# Power.net
KiCad netlist of a schematic drawn in Altium Designer
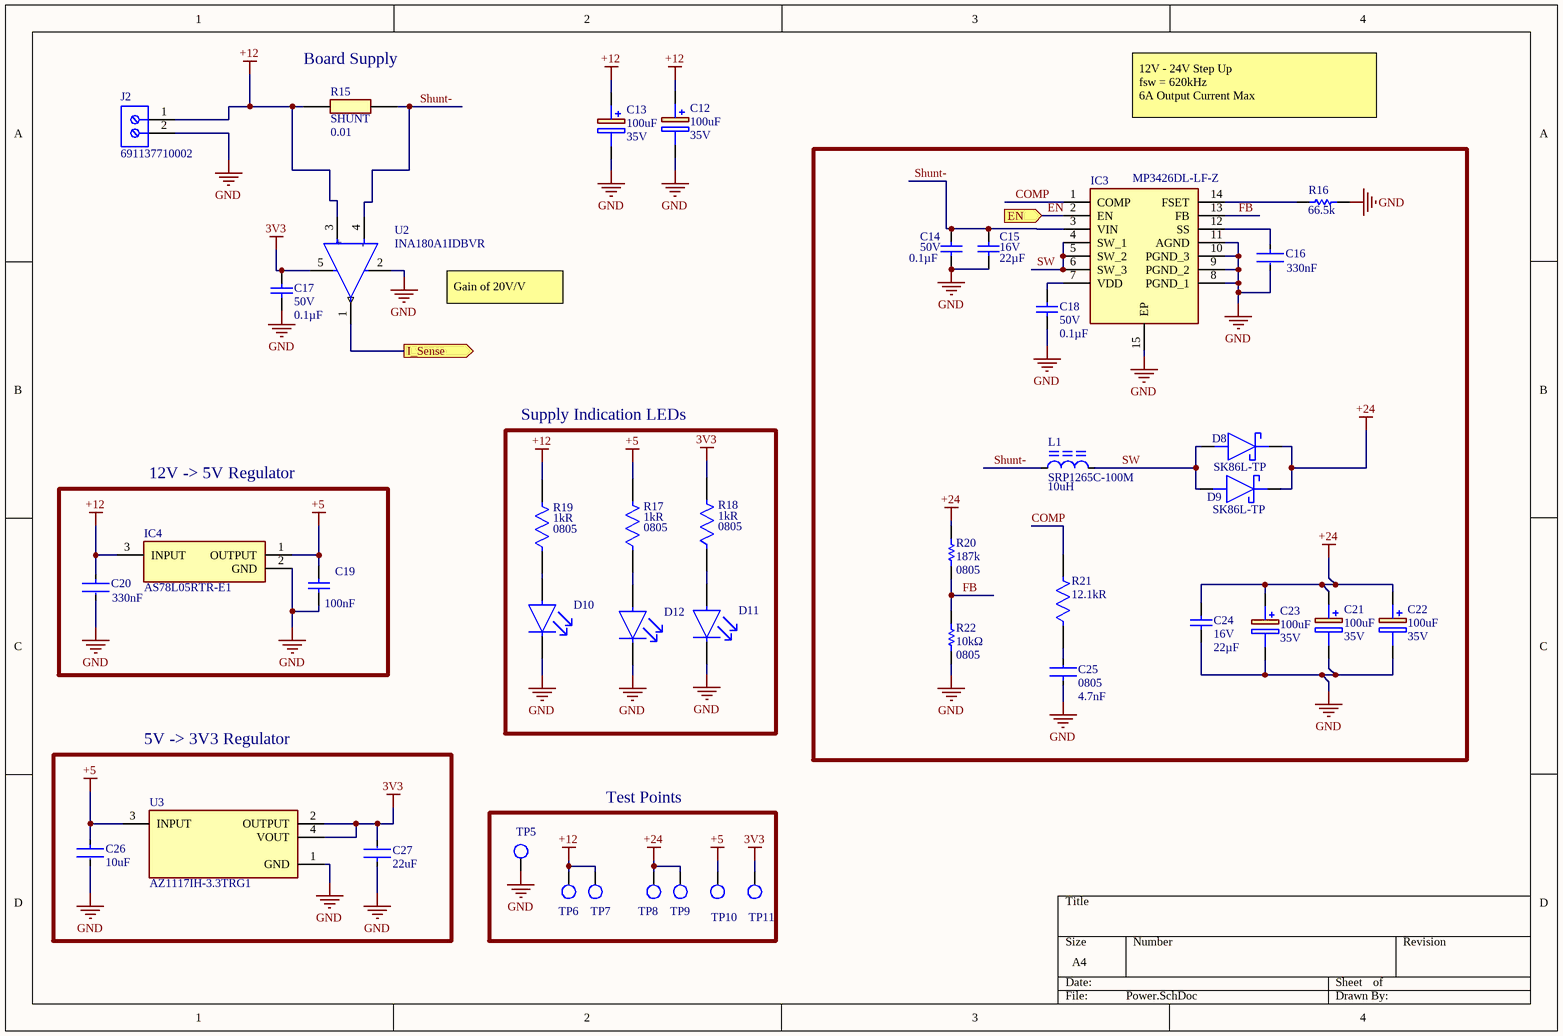
[diagram p0: Power.SchDoc]

(export (version "E")
  (design (tool "Eeschema 10.0.6"))
  (components
    (comp (ref "C12")
      (value "860010573007")
      (footprint "SamacSys:CAPPRD250W52D630H1250")
      (description "Capacitor Polarised")
      (fields
        (field (name "MOUSER PART NUMBER") "710-860010573007")
        (field (name "CAPACITANCE") "100uF")
        (field (name "VOLTAGE RATING") "35V")
      )
      (libsource (lib "*") (part "860010573007"))
    )
    (comp (ref "C13")
      (value "860010573007")
      (footprint "SamacSys:CAPPRD250W52D630H1250")
      (description "Capacitor Polarised")
      (fields
        (field (name "MOUSER PART NUMBER") "710-860010573007")
        (field (name "CAPACITANCE") "100uF")
        (field (name "VOLTAGE RATING") "35V")
      )
      (libsource (lib "*") (part "860010573007"))
    )
    (comp (ref "C14")
      (value "C0805C104K5RACTU")
      (footprint "CAP0805")
      (description "CAP CER 0.1UF 50V X7R 0805")
      (fields
        (field (name "TOLERANCE") "±10%")
        (field (name "VOLTAGE - RATED") "50V")
        (field (name "CAPACITANCE") "0.1µF")
      )
      (libsource (lib "Capacitors") (part "C0805C104K5RACTU"))
    )
    (comp (ref "C15")
      (value "CL21A226MOCLRNC")
      (footprint "CAP0805")
      (description "CAP CER 22UF 16V X5R 0805")
      (fields
        (field (name "TOLERANCE") "±20%")
        (field (name "VOLTAGE - RATED") "16V")
        (field (name "CAPACITANCE") "22µF")
      )
      (libsource (lib "Capacitors") (part "CL21A226MOCLRNC"))
    )
    (comp (ref "C16")
      (value "CL21B334KBFNNNE")
      (footprint "FP-CL21-F-IPC_C")
      (description "CAP CER 0.33UF 50V X7R 0805")
      (fields
        (field (name "CAPACITANCE") "330nF")
        (field (name "MANUFACTURER") "Samsung Electro-Mechanics")
        (field (name "OCTOPART") "https://octopart.com/cl21b334kbfnnne-samsung-9287149")
      )
      (libsource (lib "Altium Content Vault") (part "11868f565c42a9108669ba33697ecf6"))
    )
    (comp (ref "C17")
      (value "C0805C104K5RACTU")
      (footprint "CAP0805")
      (description "CAP CER 0.1UF 50V X7R 0805")
      (fields
        (field (name "TOLERANCE") "±10%")
        (field (name "VOLTAGE - RATED") "50V")
        (field (name "CAPACITANCE") "0.1µF")
      )
      (libsource (lib "Capacitors") (part "C0805C104K5RACTU"))
    )
    (comp (ref "C18")
      (value "C0805C104K5RACTU")
      (footprint "CAP0805")
      (description "CAP CER 0.1UF 50V X7R 0805")
      (fields
        (field (name "TOLERANCE") "±10%")
        (field (name "VOLTAGE - RATED") "50V")
        (field (name "CAPACITANCE") "0.1µF")
      )
      (libsource (lib "Capacitors") (part "C0805C104K5RACTU"))
    )
    (comp (ref "C19")
      (value "08055D104KAT2A")
      (footprint "CAPC2013X140X50ML20T25")
      (fields (field (name "MANUFACTURER") "AVX Interconnect / Elco") (field (name "CAPACITANCE") "100nF"))
      (libsource (lib "Altium Content Vault") (part "CAP"))
    )
    (comp (ref "C20")
      (value "CL21B334KBFNNNE")
      (footprint "FP-CL21-F-IPC_C")
      (description "CAP CER 0.33UF 50V X7R 0805")
      (fields
        (field (name "CAPACITANCE") "330nF")
        (field (name "MANUFACTURER") "Samsung Electro-Mechanics")
        (field (name "OCTOPART") "https://octopart.com/cl21b334kbfnnne-samsung-9287149")
      )
      (libsource (lib "Altium Content Vault") (part "11868f565c42a9108669ba33697ecf6"))
    )
    (comp (ref "C21")
      (value "860010573007")
      (footprint "SamacSys:CAPPRD250W52D630H1250")
      (description "Capacitor Polarised")
      (fields
        (field (name "MOUSER PART NUMBER") "710-860010573007")
        (field (name "CAPACITANCE") "100uF")
        (field (name "VOLTAGE RATING") "35V")
      )
      (libsource (lib "*") (part "860010573007"))
    )
    (comp (ref "C22")
      (value "860010573007")
      (footprint "SamacSys:CAPPRD250W52D630H1250")
      (description "Capacitor Polarised")
      (fields
        (field (name "MOUSER PART NUMBER") "710-860010573007")
        (field (name "CAPACITANCE") "100uF")
        (field (name "VOLTAGE RATING") "35V")
      )
      (libsource (lib "*") (part "860010573007"))
    )
    (comp (ref "C23")
      (value "860010573007")
      (footprint "SamacSys:CAPPRD250W52D630H1250")
      (description "Capacitor Polarised")
      (fields
        (field (name "MOUSER PART NUMBER") "710-860010573007")
        (field (name "CAPACITANCE") "100uF")
        (field (name "VOLTAGE RATING") "35V")
      )
      (libsource (lib "*") (part "860010573007"))
    )
    (comp (ref "C24")
      (value "CL21A226MOCLRNC")
      (footprint "CAP0805")
      (description "CAP CER 22UF 16V X5R 0805")
      (fields
        (field (name "TOLERANCE") "±20%")
        (field (name "VOLTAGE - RATED") "16V")
        (field (name "CAPACITANCE") "22µF")
      )
      (libsource (lib "Capacitors") (part "CL21A226MOCLRNC"))
    )
    (comp (ref "C25")
      (value "CL21B472KBANNNC")
      (footprint "FP-CL21-IPC_A")
      (description "CL21 Series 0805 4.7nF 50V ±10% Tolerance X7R Multilayer Ceramic Chip Capacitor")
      (fields
        (field (name "CASE CODE (IMPERIAL)") "0805")
        (field (name "TOLERANCE") "10%")
        (field (name "CAPACITANCE") "4.7nF")
        (field (name "VOLTAGE") "50V")
      )
      (libsource (lib "Altium Content Vault") (part "b4654b650e69147ec39a6b967a45e02"))
    )
    (comp (ref "C26")
      (value "CL21A106KOQNNNE")
      (footprint "FP-CL21-IPC_B")
      (description "CL21 Series 0805 10uF 16V ±10% Tolerance X5R Multilayer Ceramic Chip Capacitor")
      (fields
        (field (name "VOLTAGE") "16V")
        (field (name "CAPACITANCE") "10uF")
        (field (name "TOLERANCE") "10%")
      )
      (libsource (lib "Altium Content Vault") (part "b4654b650e69147ec39a6b967a45e02"))
    )
    (comp (ref "C27")
      (value "CL21A226MQQNNNG")
      (footprint "FP-CL21-IPC_B")
      (description "CL21 Series 0805 22uF 6.3V ±20% Tolerance X5R Multilayer Ceramic Chip Capacitor")
      (fields
        (field (name "TOLERANCE") "20%")
        (field (name "CAPACITANCE") "22uF")
        (field (name "VOLTAGE") "6.3V")
      )
      (libsource (lib "Altium Content Vault") (part "b4654b650e69147ec39a6b967a45e02"))
    )
    (comp (ref "D8")
      (value "SK86L-TP")
      (footprint "SamacSys:DIOM7959X262N")
      (description "Schottky Diode")
      (fields (field (name "MOUSER PART NUMBER") "833-SK86L-TP"))
      (libsource (lib "*") (part "SK86L-TP"))
    )
    (comp (ref "D9")
      (value "SK86L-TP")
      (footprint "SamacSys:DIOM7959X262N")
      (description "Schottky Diode")
      (fields (field (name "MOUSER PART NUMBER") "833-SK86L-TP"))
      (libsource (lib "*") (part "SK86L-TP"))
    )
    (comp (ref "D10")
      (value "150060VS75000")
      (footprint "FP-150060VS75000-MFG")
      (description "LED GREEN CLEAR 0603 SMD")
      (libsource (lib "Altium Content Vault") (part "8706943c75ba83719d021d2fdc84c58"))
    )
    (comp (ref "D11")
      (value "150060VS75000")
      (footprint "FP-150060VS75000-MFG")
      (description "LED GREEN CLEAR 0603 SMD")
      (libsource (lib "Altium Content Vault") (part "8706943c75ba83719d021d2fdc84c58"))
    )
    (comp (ref "D12")
      (value "150060VS75000")
      (footprint "FP-150060VS75000-MFG")
      (description "LED GREEN CLEAR 0603 SMD")
      (libsource (lib "Altium Content Vault") (part "8706943c75ba83719d021d2fdc84c58"))
    )
    (comp (ref "IC3")
      (value "MP3426DL-LF-Z")
      (footprint "SamacSys:SON50P300X400X100-15N-D")
      (description "Integrated Circuit")
      (fields (field (name "MOUSER PART NUMBER") "946-MP3426DL-LF-Z"))
      (libsource (lib "*") (part "MP3426DL-LF-Z"))
    )
    (comp (ref "IC4")
      (value "AS78L05RTR-E1")
      (footprint "WPT_Transmitter_lib:DIODES_SOT-89")
      (description "Integrated Circuit")
      (fields (field (name "MOUSER PART NUMBER") "621-AS78L05RTR-E1"))
      (libsource (lib "WPT_Transmitter_lib") (part "AS78L05RTR-E1"))
    )
    (comp (ref "J2")
      (value "691137710002")
      (footprint "691137710002")
      (description "Series 1377 - 5.00 mm Horizontal Entry with Pressure Clamp WR-TBL, 2 pin")
      (fields (field (name "MANUFACTURER") "Wurth Elektronik") (field (name "PUBLISHER") "WurthElektronik"))
      (libsource (lib "Altium Content Vault") (part "WE-CN-1P-F-TB2"))
    )
    (comp (ref "L1")
      (value "SRP1265C-100M")
      (footprint "FP-SRP1265C-MFG")
      (description "FIXED IND 10UH 12A 18 MOHM SMD")
      (fields (field (name "INDUCTANCE") "10uH"))
      (libsource (lib "Altium Content Vault") (part "6c39b3e99e391d93b685d58a9117a12"))
    )
    (comp (ref "R15")
      (value "SHUNT")
      (footprint "SamacSys:RESC6434X90N")
      (description "Resistor")
      (fields
        (field (name "MANUFACTURER_PART_NUMBER") "CRA2512-FZ-R010ELF")
        (field (name "MOUSER PART NUMBER") "652-CRA2512FZR010ELF")
        (field (name "RESISTANCE") "0.01")
      )
      (libsource (lib "*") (part "CRA2512-FZ-R010ELF"))
    )
    (comp (ref "R16")
      (value "ERJ-6ENF6652V")
      (footprint "RESC2013X70X40LL20T20")
      (fields (field (name "MANUFACTURER") "Panasonic") (field (name "RESISTANCE") "66.5k"))
      (libsource (lib "Altium Content Vault") (part "RES"))
    )
    (comp (ref "R17")
      (value "RNCP0805FTD1K00")
      (footprint "FP-RNCP0805-MFG")
      (description "1kΩ ±1% 0.25W 0805 High Power Anti-Sulfur Thin Film Chip Resistor")
      (fields
        (field (name "RESISTANCE") "1kR")
        (field (name "SIZE CODE") "0805")
        (field (name "TOLERANCE") "1%")
      )
      (libsource (lib "Altium Content Vault") (part "1029c3af85768c4190bb7ad29bc67b5"))
    )
    (comp (ref "R18")
      (value "RNCP0805FTD1K00")
      (footprint "FP-RNCP0805-MFG")
      (description "1kΩ ±1% 0.25W 0805 High Power Anti-Sulfur Thin Film Chip Resistor")
      (fields
        (field (name "RESISTANCE") "1kR")
        (field (name "SIZE CODE") "0805")
        (field (name "TOLERANCE") "1%")
      )
      (libsource (lib "Altium Content Vault") (part "1029c3af85768c4190bb7ad29bc67b5"))
    )
    (comp (ref "R19")
      (value "RNCP0805FTD1K00")
      (footprint "FP-RNCP0805-MFG")
      (description "1kΩ ±1% 0.25W 0805 High Power Anti-Sulfur Thin Film Chip Resistor")
      (fields
        (field (name "RESISTANCE") "1kR")
        (field (name "SIZE CODE") "0805")
        (field (name "TOLERANCE") "1%")
      )
      (libsource (lib "Altium Content Vault") (part "1029c3af85768c4190bb7ad29bc67b5"))
    )
    (comp (ref "R20")
      (value "ERJ-6ENF1873V")
      (footprint "RESC2013X70X40NL20T20")
      (fields
        (field (name "MANUFACTURER") "Panasonic")
        (field (name "RESISTANCE") "187k")
        (field (name "PACKAGE") "0805")
      )
      (libsource (lib "Altium Content Vault") (part "RES"))
    )
    (comp (ref "R21")
      (value "RNCP0805FTD12K1")
      (footprint "FP-RNCP0805-IPC_B")
      (description "12.1kΩ ±1% 0.25W 0805 High Power Anti-Sulfur Thin Film Chip Resistor")
      (fields (field (name "RESISTANCE") "12.1kR") (field (name "TOLERANCE") "1%"))
      (libsource (lib "Altium Content Vault") (part "1029c3af85768c4190bb7ad29bc67b5"))
    )
    (comp (ref "R22")
      (value "RC0805FR-0710KL")
      (footprint "RES0805")
      (description "RES SMD 10K OHM 1% 1/8W 0805")
      (fields
        (field (name "MANUFACTURER") "Yageo")
        (field (name "TOLERANCE") "±1%")
        (field (name "RESISTANCE") "10kΩ")
        (field (name "PACKAGE / CASE") "0805")
      )
      (libsource (lib "Resistors") (part "RC0805FR-0710KL"))
    )
    (comp (ref "TP5")
      (value "GND")
      (footprint "TESTPOINT_LOOP")
      (description "PC TEST POINT MINIATURE WHITE")
      (libsource (lib "Connectors and Headers") (part "TESTPOINT_LOOP"))
    )
    (comp (ref "TP6")
      (value "12V")
      (footprint "TESTPOINT_LOOP")
      (description "PC TEST POINT MINIATURE WHITE")
      (libsource (lib "Connectors and Headers") (part "TESTPOINT_LOOP"))
    )
    (comp (ref "TP7")
      (value "12V")
      (footprint "TESTPOINT_LOOP")
      (description "PC TEST POINT MINIATURE WHITE")
      (libsource (lib "Connectors and Headers") (part "TESTPOINT_LOOP"))
    )
    (comp (ref "TP8")
      (value "24V")
      (footprint "TESTPOINT_LOOP")
      (description "PC TEST POINT MINIATURE WHITE")
      (libsource (lib "Connectors and Headers") (part "TESTPOINT_LOOP"))
    )
    (comp (ref "TP9")
      (value "24V")
      (footprint "TESTPOINT_LOOP")
      (description "PC TEST POINT MINIATURE WHITE")
      (libsource (lib "Connectors and Headers") (part "TESTPOINT_LOOP"))
    )
    (comp (ref "TP10")
      (value "5V")
      (footprint "TESTPOINT_LOOP")
      (description "PC TEST POINT MINIATURE WHITE")
      (libsource (lib "Connectors and Headers") (part "TESTPOINT_LOOP"))
    )
    (comp (ref "TP11")
      (value "3V3")
      (footprint "TESTPOINT_LOOP")
      (description "PC TEST POINT MINIATURE WHITE")
      (libsource (lib "Connectors and Headers") (part "TESTPOINT_LOOP"))
    )
    (comp (ref "U2")
      (value "INA180A1IDBVR")
      (footprint "FP-DBV0005A-IPC_A")
      (description "IC CURR SENSE 1 CIRCUIT SOT23-5")
      (libsource (lib "Altium Content Vault") (part "0a55cf1a948ad01a3239aec1b7efad0"))
    )
    (comp (ref "U3")
      (value "AZ1117IH-3.3TRG1")
      (footprint "FP-SOT223-IPC_B")
      (description "IC REG LINEAR 3.3V 1A SOT223")
      (libsource (lib "Altium Content Vault") (part "3c8a0cc3f7d1fafcf032f21e1bb5f65"))
    )
  )
  (nets
    (net (code "1") (name "+5") (class "Default")
      (node (ref "C19") (pin "2") (pinfunction "2_2") (pintype "passive"))
      (node (ref "C26") (pin "1") (pinfunction "1_1") (pintype "passive"))
      (node (ref "IC4") (pin "1") (pinfunction "OUTPUT_1") (pintype "passive"))
      (node (ref "R17") (pin "2") (pinfunction "2_2") (pintype "passive"))
      (node (ref "TP10") (pin "1") (pintype "passive"))
      (node (ref "U3") (pin "3") (pinfunction "INPUT_3") (pintype "power_in"))
    )
    (net (code "2") (name "+12") (class "Default")
      (node (ref "C12") (pin "1") (pinfunction "+_1") (pintype "passive"))
      (node (ref "C13") (pin "1") (pinfunction "+_1") (pintype "passive"))
      (node (ref "C20") (pin "1") (pinfunction "1_1") (pintype "passive"))
      (node (ref "IC4") (pin "3") (pinfunction "INPUT_3") (pintype "passive"))
      (node (ref "J2") (pin "1") (pinfunction "1_1") (pintype "passive"))
      (node (ref "R15") (pin "1") (pinfunction "1_1") (pintype "passive"))
      (node (ref "R19") (pin "2") (pinfunction "2_2") (pintype "passive"))
      (node (ref "TP6") (pin "1") (pintype "passive"))
      (node (ref "TP7") (pin "1") (pintype "passive"))
      (node (ref "U2") (pin "3") (pinfunction "IN+_3") (pintype "tri_state"))
    )
    (net (code "3") (name "+24") (class "Default")
      (node (ref "C21") (pin "1") (pinfunction "+_1") (pintype "passive"))
      (node (ref "C22") (pin "1") (pinfunction "+_1") (pintype "passive"))
      (node (ref "C23") (pin "1") (pinfunction "+_1") (pintype "passive"))
      (node (ref "C24") (pin "2") (pinfunction "2_2") (pintype "passive"))
      (node (ref "D8") (pin "1") (pinfunction "K_1") (pintype "passive"))
      (node (ref "D9") (pin "1") (pinfunction "K_1") (pintype "passive"))
      (node (ref "R20") (pin "1") (pinfunction "1_1") (pintype "passive"))
      (node (ref "TP8") (pin "1") (pintype "passive"))
      (node (ref "TP9") (pin "1") (pintype "passive"))
    )
    (net (code "4") (name "/COMP") (class "Default")
      (node (ref "IC3") (pin "1") (pinfunction "COMP_1") (pintype "passive"))
      (node (ref "R21") (pin "2") (pinfunction "2_2") (pintype "passive"))
    )
    (net (code "5") (name "/EN") (class "Default")
      (node (ref "IC3") (pin "2") (pinfunction "EN_2") (pintype "passive"))
    )
    (net (code "6") (name "/FB") (class "Default")
      (node (ref "IC3") (pin "13") (pinfunction "FB_13") (pintype "passive"))
      (node (ref "R20") (pin "2") (pinfunction "2_2") (pintype "passive"))
      (node (ref "R22") (pin "2") (pinfunction "2_2") (pintype "passive"))
    )
    (net (code "7") (name "/I_Sense") (class "Default")
      (node (ref "U2") (pin "1") (pinfunction "OUT_1") (pintype "output"))
    )
    (net (code "8") (name "/SW") (class "Default")
      (node (ref "D8") (pin "2") (pinfunction "A_2") (pintype "passive"))
      (node (ref "D9") (pin "2") (pinfunction "A_2") (pintype "passive"))
      (node (ref "IC3") (pin "4") (pinfunction "SW_1_4") (pintype "passive"))
      (node (ref "IC3") (pin "5") (pinfunction "SW_2_5") (pintype "passive"))
      (node (ref "IC3") (pin "6") (pinfunction "SW_3_6") (pintype "passive"))
      (node (ref "L1") (pin "2") (pinfunction "2_2") (pintype "passive"))
    )
    (net (code "9") (name "/Shunt-") (class "Default")
      (node (ref "C14") (pin "2") (pinfunction "2_2") (pintype "passive"))
      (node (ref "C15") (pin "2") (pinfunction "2_2") (pintype "passive"))
      (node (ref "IC3") (pin "3") (pinfunction "VIN_3") (pintype "passive"))
      (node (ref "L1") (pin "1") (pinfunction "1_1") (pintype "passive"))
      (node (ref "R15") (pin "2") (pinfunction "2_2") (pintype "passive"))
      (node (ref "U2") (pin "4") (pinfunction "IN-_4") (pintype "tri_state"))
    )
    (net (code "10") (name "3V3") (class "Default")
      (node (ref "C17") (pin "2") (pinfunction "2_2") (pintype "passive"))
      (node (ref "C27") (pin "2") (pinfunction "2_2") (pintype "passive"))
      (node (ref "R18") (pin "2") (pinfunction "2_2") (pintype "passive"))
      (node (ref "TP11") (pin "1") (pintype "passive"))
      (node (ref "U2") (pin "5") (pinfunction "VS_5") (pintype "power_in"))
      (node (ref "U3") (pin "2") (pinfunction "OUTPUT_2") (pintype "power_in"))
      (node (ref "U3") (pin "4") (pinfunction "VOUT_4") (pintype "power_in"))
    )
    (net (code "11") (name "GND") (class "Default")
      (node (ref "C12") (pin "2") (pinfunction "-_2") (pintype "passive"))
      (node (ref "C13") (pin "2") (pinfunction "-_2") (pintype "passive"))
      (node (ref "C14") (pin "1") (pinfunction "1_1") (pintype "passive"))
      (node (ref "C15") (pin "1") (pinfunction "1_1") (pintype "passive"))
      (node (ref "C16") (pin "2") (pinfunction "2_2") (pintype "passive"))
      (node (ref "C17") (pin "1") (pinfunction "1_1") (pintype "passive"))
      (node (ref "C18") (pin "1") (pinfunction "1_1") (pintype "passive"))
      (node (ref "C19") (pin "1") (pinfunction "1_1") (pintype "passive"))
      (node (ref "C20") (pin "2") (pinfunction "2_2") (pintype "passive"))
      (node (ref "C21") (pin "2") (pinfunction "-_2") (pintype "passive"))
      (node (ref "C22") (pin "2") (pinfunction "-_2") (pintype "passive"))
      (node (ref "C23") (pin "2") (pinfunction "-_2") (pintype "passive"))
      (node (ref "C24") (pin "1") (pinfunction "1_1") (pintype "passive"))
      (node (ref "C25") (pin "1") (pinfunction "1_1") (pintype "passive"))
      (node (ref "C26") (pin "2") (pinfunction "2_2") (pintype "passive"))
      (node (ref "C27") (pin "1") (pinfunction "1_1") (pintype "passive"))
      (node (ref "D10") (pin "1") (pinfunction "C_1") (pintype "passive"))
      (node (ref "D11") (pin "1") (pinfunction "C_1") (pintype "passive"))
      (node (ref "D12") (pin "1") (pinfunction "C_1") (pintype "passive"))
      (node (ref "IC3") (pin "10") (pinfunction "PGND_3_10") (pintype "passive"))
      (node (ref "IC3") (pin "11") (pinfunction "AGND_11") (pintype "passive"))
      (node (ref "IC3") (pin "15") (pinfunction "EP_15") (pintype "passive"))
      (node (ref "IC3") (pin "8") (pinfunction "PGND_1_8") (pintype "passive"))
      (node (ref "IC3") (pin "9") (pinfunction "PGND_2_9") (pintype "passive"))
      (node (ref "IC4") (pin "2") (pinfunction "GND_2") (pintype "passive"))
      (node (ref "J2") (pin "2") (pinfunction "2_2") (pintype "passive"))
      (node (ref "R16") (pin "1") (pinfunction "1_1") (pintype "passive"))
      (node (ref "R22") (pin "1") (pinfunction "1_1") (pintype "passive"))
      (node (ref "TP5") (pin "1") (pintype "passive"))
      (node (ref "U2") (pin "2") (pinfunction "GND_2") (pintype "power_in"))
      (node (ref "U3") (pin "1") (pinfunction "GND_1") (pintype "power_in"))
    )
    (net (code "12") (name "Net-(C25-Pad2)") (class "Default")
      (node (ref "C25") (pin "2") (pinfunction "2_2") (pintype "passive"))
      (node (ref "R21") (pin "1") (pinfunction "1_1") (pintype "passive"))
    )
    (net (code "13") (name "Net-(D10-A)") (class "Default")
      (node (ref "D10") (pin "2") (pinfunction "A_2") (pintype "passive"))
      (node (ref "R19") (pin "1") (pinfunction "1_1") (pintype "passive"))
    )
    (net (code "14") (name "Net-(D11-A)") (class "Default")
      (node (ref "D11") (pin "2") (pinfunction "A_2") (pintype "passive"))
      (node (ref "R18") (pin "1") (pinfunction "1_1") (pintype "passive"))
    )
    (net (code "15") (name "Net-(D12-A)") (class "Default")
      (node (ref "D12") (pin "2") (pinfunction "A_2") (pintype "passive"))
      (node (ref "R17") (pin "1") (pinfunction "1_1") (pintype "passive"))
    )
    (net (code "16") (name "Net-(IC3-FSET)") (class "Default")
      (node (ref "IC3") (pin "14") (pinfunction "FSET_14") (pintype "passive"))
      (node (ref "R16") (pin "2") (pinfunction "2_2") (pintype "passive"))
    )
    (net (code "17") (name "Net-(IC3-SS)") (class "Default")
      (node (ref "C16") (pin "1") (pinfunction "1_1") (pintype "passive"))
      (node (ref "IC3") (pin "12") (pinfunction "SS_12") (pintype "passive"))
    )
    (net (code "18") (name "Net-(IC3-VDD)") (class "Default")
      (node (ref "C18") (pin "2") (pinfunction "2_2") (pintype "passive"))
      (node (ref "IC3") (pin "7") (pinfunction "VDD_7") (pintype "passive"))
    )
  )
)
